# SCH_50Hz.net
KiCad netlist of a schematic drawn in EasyEDA
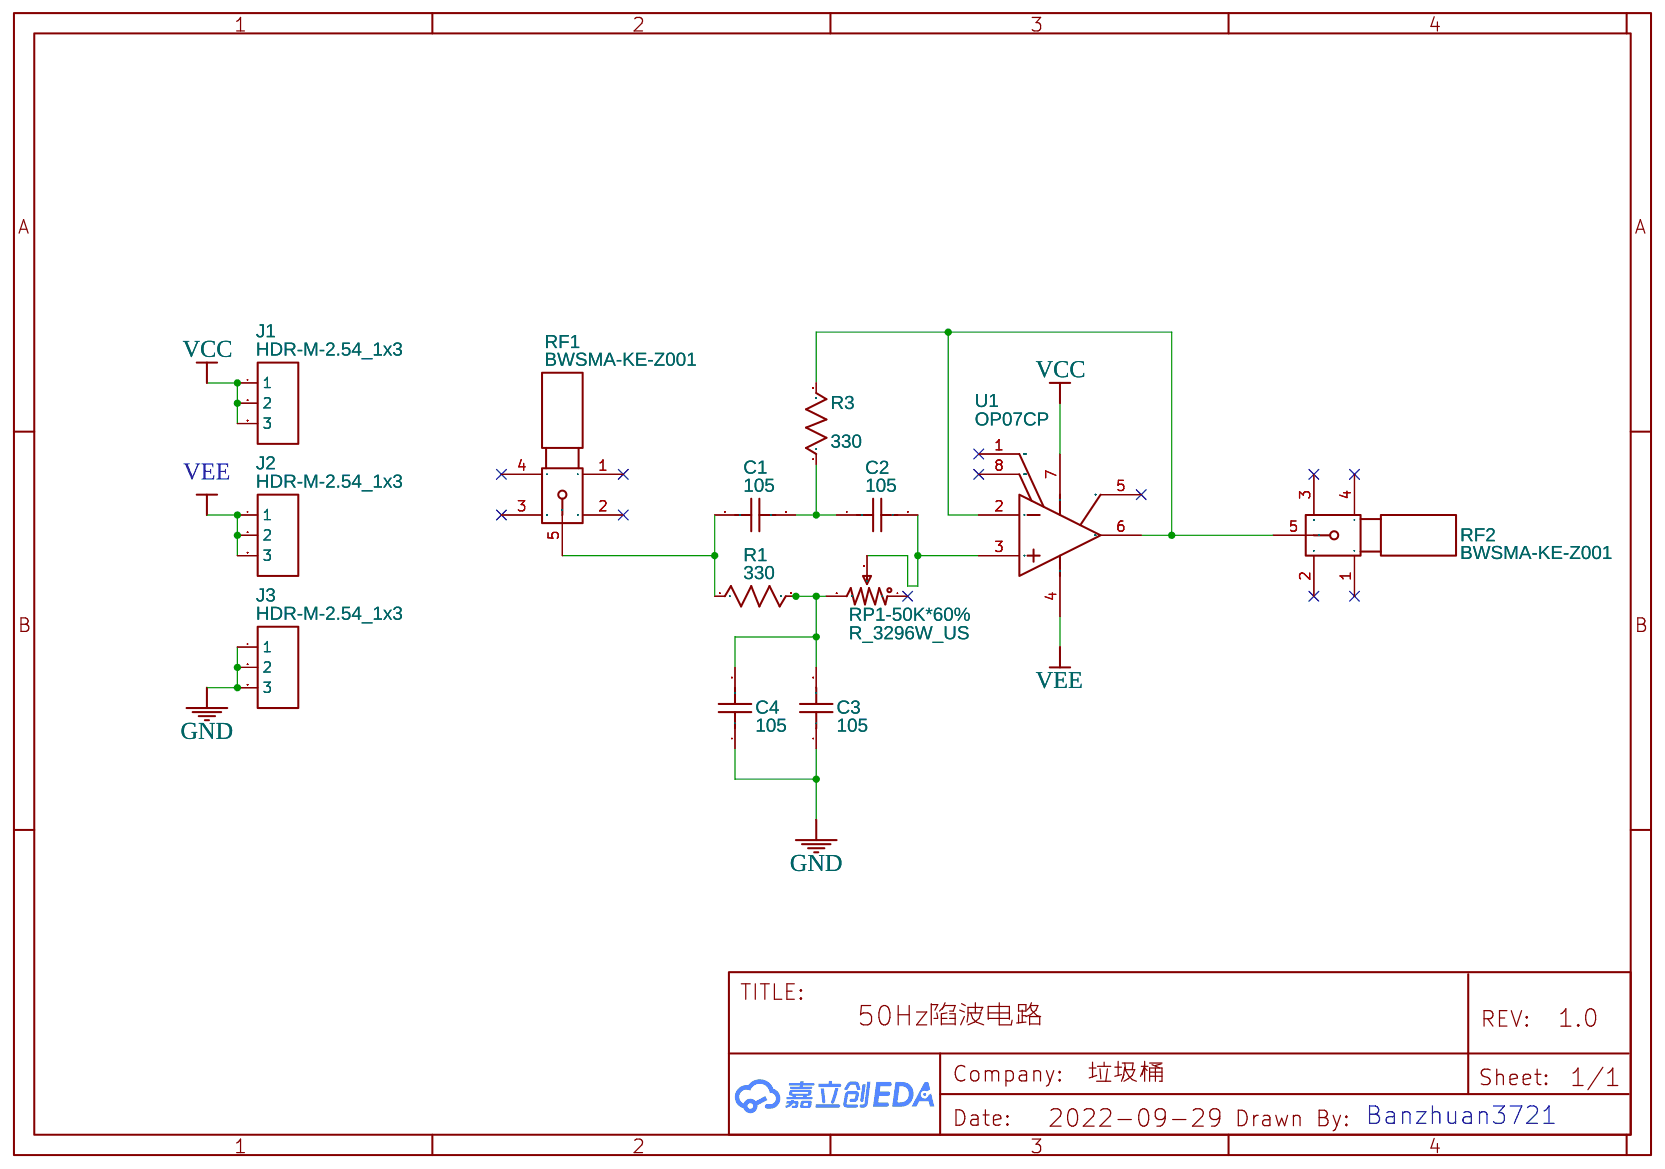
[diagram p0: schematic sheet]

(export (version "E")
  (design (tool "Eeschema 10.0.6"))
  (components
    (comp (ref "C1") (value "105") (libsource (lib "") (part "C_RAD-0.2_US")))
    (comp (ref "C2") (value "105") (libsource (lib "") (part "C_RAD-0.2_US")))
    (comp (ref "C3") (value "105") (libsource (lib "") (part "C_RAD-0.2_US_1")))
    (comp (ref "C4") (value "105") (libsource (lib "") (part "C_RAD-0.2_US_1")))
    (comp (ref "J1")
      (value "HDR-M-2.54_1x3")
      (fields (field (name "BOM_Supplier Part") "C180248"))
      (libsource (lib "") (part "HDR-M-2.54_1x3"))
    )
    (comp (ref "J2")
      (value "HDR-M-2.54_1x3")
      (fields (field (name "BOM_Supplier Part") "C180248"))
      (libsource (lib "") (part "HDR-M-2.54_1x3"))
    )
    (comp (ref "J3")
      (value "HDR-M-2.54_1x3")
      (fields (field (name "BOM_Supplier Part") "C180248"))
      (libsource (lib "") (part "HDR-M-2.54_1x3"))
    )
    (comp (ref "R1") (value "330") (libsource (lib "") (part "R_AXIAL-0.3_US")))
    (comp (ref "R3") (value "330") (libsource (lib "") (part "R_AXIAL-0.3_US_1")))
    (comp (ref "RF1")
      (value "BWSMA-KE-Z001")
      (fields (field (name "BOM_Supplier Part") "C496549"))
      (libsource (lib "") (part "BWSMA-KE-Z001"))
    )
    (comp (ref "RF2")
      (value "BWSMA-KE-Z001")
      (fields (field (name "BOM_Supplier Part") "C496549"))
      (libsource (lib "") (part "BWSMA-KE-Z001_1"))
    )
    (comp (ref "RP1-50K*60%") (value "R_3296W_US") (libsource (lib "") (part "R_3296W_US")))
    (comp (ref "U1")
      (value "OP07CP")
      (fields (field (name "BOM_Supplier Part") "C5224"))
      (libsource (lib "") (part "OP07CP"))
    )
  )
  (nets
    (net (code "1") (name "GND") (class "Default")
      (node (ref "C3") (pin "1") (pinfunction "1_1") (pintype "unspecified"))
      (node (ref "C4") (pin "1") (pinfunction "1_1") (pintype "unspecified"))
      (node (ref "J3") (pin "1") (pinfunction "1_1") (pintype "input"))
      (node (ref "J3") (pin "2") (pinfunction "2_2") (pintype "input"))
      (node (ref "J3") (pin "3") (pinfunction "3_3") (pintype "input"))
    )
    (net (code "2") (name "Net-(C1-Pad1)") (class "Default")
      (node (ref "C1") (pin "1") (pinfunction "1_1") (pintype "unspecified"))
      (node (ref "R1") (pin "1") (pinfunction "1_1") (pintype "unspecified"))
      (node (ref "RF1") (pin "5") (pinfunction "5_5") (pintype "unspecified"))
    )
    (net (code "3") (name "Net-(C1-Pad2)") (class "Default")
      (node (ref "C1") (pin "2") (pinfunction "2_2") (pintype "unspecified"))
      (node (ref "C2") (pin "1") (pinfunction "1_1") (pintype "unspecified"))
      (node (ref "R3") (pin "1") (pinfunction "1_1") (pintype "unspecified"))
    )
    (net (code "4") (name "Net-(C3-Pad2)") (class "Default")
      (node (ref "C3") (pin "2") (pinfunction "2_2") (pintype "unspecified"))
      (node (ref "C4") (pin "2") (pinfunction "2_2") (pintype "unspecified"))
      (node (ref "R1") (pin "2") (pinfunction "2_2") (pintype "unspecified"))
      (node (ref "RP1-50K*60%") (pin "3") (pinfunction "3_3") (pintype "unspecified"))
    )
    (net (code "5") (name "Net-(U1-IN+)") (class "Default")
      (node (ref "C2") (pin "2") (pinfunction "2_2") (pintype "unspecified"))
      (node (ref "RP1-50K*60%") (pin "2") (pinfunction "2_2") (pintype "unspecified"))
      (node (ref "U1") (pin "3") (pinfunction "IN+_3") (pintype "unspecified"))
    )
    (net (code "6") (name "Net-(U1-IN-)") (class "Default")
      (node (ref "R3") (pin "2") (pinfunction "2_2") (pintype "unspecified"))
      (node (ref "RF2") (pin "5") (pinfunction "5_5") (pintype "unspecified"))
      (node (ref "U1") (pin "2") (pinfunction "IN-_2") (pintype "unspecified"))
      (node (ref "U1") (pin "6") (pinfunction "OUT_6") (pintype "output"))
    )
    (net (code "7") (name "VCC") (class "Default")
      (node (ref "J1") (pin "1") (pinfunction "1_1") (pintype "input"))
      (node (ref "J1") (pin "2") (pinfunction "2_2") (pintype "input"))
      (node (ref "J1") (pin "3") (pinfunction "3_3") (pintype "input"))
      (node (ref "U1") (pin "7") (pinfunction "VCC+_7") (pintype "passive"))
    )
    (net (code "8") (name "VEE") (class "Default")
      (node (ref "J2") (pin "1") (pinfunction "1_1") (pintype "input"))
      (node (ref "J2") (pin "2") (pinfunction "2_2") (pintype "input"))
      (node (ref "J2") (pin "3") (pinfunction "3_3") (pintype "input"))
      (node (ref "U1") (pin "4") (pinfunction "VCC-_4") (pintype "passive"))
    )
    (net (code "9") (name "unconnected-(RF1-Pad1)") (class "Default")
      (node (ref "RF1") (pin "1") (pinfunction "1_1") (pintype "unspecified+no_connect"))
    )
    (net (code "10") (name "unconnected-(RF1-Pad2)") (class "Default")
      (node (ref "RF1") (pin "2") (pinfunction "2_2") (pintype "unspecified+no_connect"))
    )
    (net (code "11") (name "unconnected-(RF1-Pad3)") (class "Default")
      (node (ref "RF1") (pin "3") (pinfunction "3_3") (pintype "unspecified+no_connect"))
    )
    (net (code "12") (name "unconnected-(RF1-Pad4)") (class "Default")
      (node (ref "RF1") (pin "4") (pinfunction "4_4") (pintype "unspecified+no_connect"))
    )
    (net (code "13") (name "unconnected-(RF2-Pad1)") (class "Default")
      (node (ref "RF2") (pin "1") (pinfunction "1_1") (pintype "unspecified+no_connect"))
    )
    (net (code "14") (name "unconnected-(RF2-Pad2)") (class "Default")
      (node (ref "RF2") (pin "2") (pinfunction "2_2") (pintype "unspecified+no_connect"))
    )
    (net (code "15") (name "unconnected-(RF2-Pad3)") (class "Default")
      (node (ref "RF2") (pin "3") (pinfunction "3_3") (pintype "unspecified+no_connect"))
    )
    (net (code "16") (name "unconnected-(RF2-Pad4)") (class "Default")
      (node (ref "RF2") (pin "4") (pinfunction "4_4") (pintype "unspecified+no_connect"))
    )
    (net (code "17") (name "unconnected-(RP1-50K*60%-Pad1)") (class "Default")
      (node (ref "RP1-50K*60%") (pin "1") (pinfunction "1_1") (pintype "unspecified+no_connect"))
    )
    (net (code "18") (name "unconnected-(U1-NC-Pad5)") (class "Default")
      (node (ref "U1") (pin "5") (pinfunction "NC_5") (pintype "unspecified+no_connect"))
    )
    (net (code "19") (name "unconnected-(U1-OFFSET_N1-Pad1)") (class "Default")
      (node (ref "U1") (pin "1") (pinfunction "OFFSET_N1_1") (pintype "unspecified+no_connect"))
    )
    (net (code "20") (name "unconnected-(U1-OFFSET_N2-Pad8)") (class "Default")
      (node (ref "U1") (pin "8") (pinfunction "OFFSET_N2_8") (pintype "unspecified+no_connect"))
    )
  )
)
